# PROCESSOR.net
KiCad netlist of a schematic drawn in Altium Designer
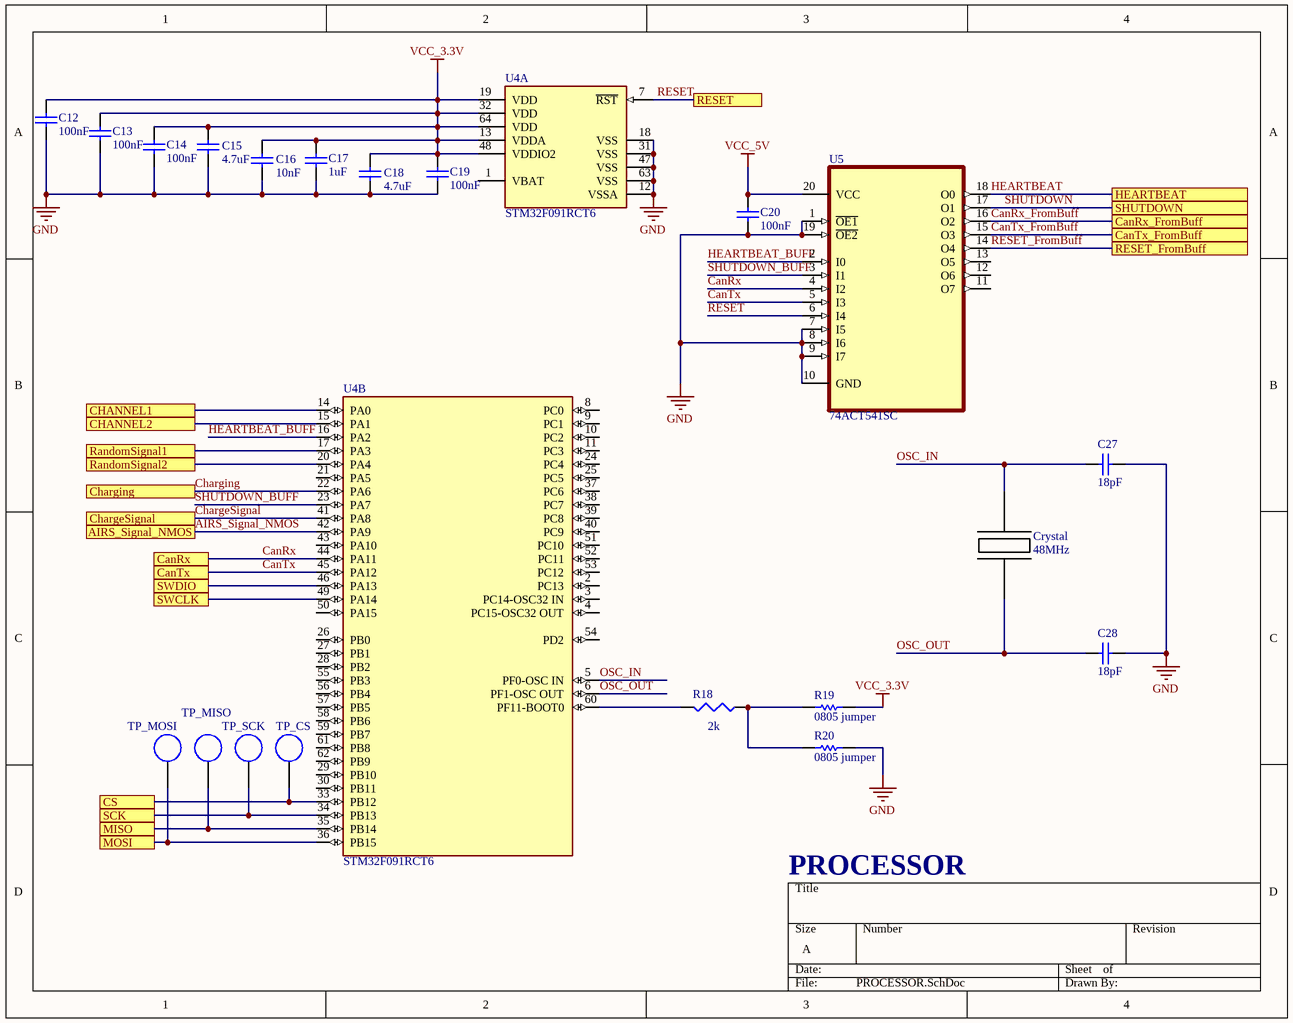
[diagram p0: PROCESSOR.SchDoc]

(export (version "E")
  (design (tool "Eeschema 10.0.6"))
  (components
    (comp (ref "C12")
      (value "100nF")
      (footprint "Cap, 5mm TH, Ceramic")
      (description "Generic Cap, 5MM TH, Ceramic")
      (fields (field (name "PUBLISHER") "T.Tallo"))
      (libsource (lib "Passives") (part "Cap, 5MM TH, Ceramic"))
    )
    (comp (ref "C13")
      (value "100nF")
      (footprint "Cap, 5mm TH, Ceramic")
      (description "Generic Cap, 5MM TH, Ceramic")
      (fields (field (name "PUBLISHER") "T.Tallo"))
      (libsource (lib "Passives") (part "Cap, 5MM TH, Ceramic"))
    )
    (comp (ref "C14")
      (value "100nF")
      (footprint "Cap, 5mm TH, Ceramic")
      (description "Generic Cap, 5MM TH, Ceramic")
      (fields (field (name "PUBLISHER") "T.Tallo"))
      (libsource (lib "Passives") (part "Cap, 5MM TH, Ceramic"))
    )
    (comp (ref "C15")
      (value "4.7uF")
      (footprint "Cap, 5mm TH, Ceramic")
      (description "Generic Cap, 5MM TH, Ceramic")
      (fields (field (name "PUBLISHER") "T.Tallo"))
      (libsource (lib "Passives") (part "Cap, 5MM TH, Ceramic"))
    )
    (comp (ref "C16")
      (value "10nF")
      (footprint "Cap, 5mm TH, Ceramic")
      (description "Generic Cap, 5MM TH, Ceramic")
      (fields (field (name "PUBLISHER") "T.Tallo"))
      (libsource (lib "Passives") (part "Cap, 5MM TH, Ceramic"))
    )
    (comp (ref "C17")
      (value "1uF")
      (footprint "Cap, 5mm TH, Ceramic")
      (description "Generic Cap, 5MM TH, Ceramic")
      (fields (field (name "PUBLISHER") "T.Tallo"))
      (libsource (lib "Passives") (part "Cap, 5MM TH, Ceramic"))
    )
    (comp (ref "C18")
      (value "4.7uF")
      (footprint "Cap, 5mm TH, Ceramic")
      (description "Generic Cap, 5MM TH, Ceramic")
      (fields (field (name "PUBLISHER") "T.Tallo"))
      (libsource (lib "Passives") (part "Cap, 5MM TH, Ceramic"))
    )
    (comp (ref "C19")
      (value "100nF")
      (footprint "Cap, 5mm TH, Ceramic")
      (description "Generic Cap, 5MM TH, Ceramic")
      (fields (field (name "PUBLISHER") "T.Tallo"))
      (libsource (lib "Passives") (part "Cap, 5MM TH, Ceramic"))
    )
    (comp (ref "C20")
      (value "100nF")
      (footprint "Cap, 5mm TH, Ceramic")
      (description "Generic Cap, 5MM TH, Ceramic")
      (fields (field (name "PUBLISHER") "T.Tallo"))
      (libsource (lib "Passives") (part "Cap, 5MM TH, Ceramic"))
    )
    (comp (ref "C27")
      (value "18pF")
      (footprint "Cap, 5mm TH, Ceramic")
      (description "Generic Cap, 5MM TH, Ceramic")
      (fields (field (name "PUBLISHER") "T.Tallo"))
      (libsource (lib "Passives") (part "Cap, 5MM TH, Ceramic"))
    )
    (comp (ref "C28")
      (value "18pF")
      (footprint "Cap, 5mm TH, Ceramic")
      (description "Generic Cap, 5MM TH, Ceramic")
      (fields (field (name "PUBLISHER") "T.Tallo"))
      (libsource (lib "Passives") (part "Cap, 5MM TH, Ceramic"))
    )
    (comp (ref "Crystal")
      (value "48MHz")
      (footprint "CrystalOscillator")
      (libsource (lib "Embedded") (part "CrystalOscillator"))
    )
    (comp (ref "R18")
      (value "2k")
      (footprint "1/4W TH Resistor")
      (description "Generic TH Resistor")
      (fields (field (name "PUBLISHER") "T.Tallo"))
      (libsource (lib "Passives") (part "Resistor, TH"))
    )
    (comp (ref "R19")
      (value "0805 jumper")
      (footprint "RESC2013X60X35LL20T20")
      (description "Chip Resistor, 0 Ohm, +/- 5%, 0.125 W, -55 to 155 degC, 0805 (2012 Metric) , RoHS, Tape and Reel")
      (fields (field (name "MANUFACTURER") "Samsung Electro-Mechanics"))
      (libsource (lib "Altium Content Vault") (part "RES-2"))
    )
    (comp (ref "R20")
      (value "0805 jumper")
      (footprint "RESC2013X60X35LL20T20")
      (description "Chip Resistor, 0 Ohm, +/- 5%, 0.125 W, -55 to 155 degC, 0805 (2012 Metric) , RoHS, Tape and Reel")
      (fields (field (name "MANUFACTURER") "Samsung Electro-Mechanics"))
      (libsource (lib "Altium Content Vault") (part "RES-2"))
    )
    (comp (ref "TP_CS")
      (value "5015")
      (footprint "5015")
      (description "SMD Test Point")
      (fields (field (name "MANUFACTURER") "Keystone Electronics") (field (name "PUBLISHER") "T.Tallo"))
      (libsource (lib "Connectors") (part "5015"))
    )
    (comp (ref "TP_MISO")
      (value "5015")
      (footprint "5015")
      (description "SMD Test Point")
      (fields (field (name "MANUFACTURER") "Keystone Electronics") (field (name "PUBLISHER") "T.Tallo"))
      (libsource (lib "Connectors") (part "5015"))
    )
    (comp (ref "TP_MOSI")
      (value "5015")
      (footprint "5015")
      (description "SMD Test Point")
      (fields (field (name "MANUFACTURER") "Keystone Electronics") (field (name "PUBLISHER") "T.Tallo"))
      (libsource (lib "Connectors") (part "5015"))
    )
    (comp (ref "TP_SCK")
      (value "5015")
      (footprint "5015")
      (description "SMD Test Point")
      (fields (field (name "MANUFACTURER") "Keystone Electronics") (field (name "PUBLISHER") "T.Tallo"))
      (libsource (lib "Connectors") (part "5015"))
    )
    (comp (ref "U4")
      (value "STM32F091RCT6")
      (footprint "FP-LQFP64-5W-MFG")
      (description "IC MCU 32BIT 256KB FLASH 64LQFP")
      (fields
        (field (name "OCTOPART") "https://octopart.com/stm32f091rct6-stmicroelectronics-51988683")
        (field (name "MANUFACTURER") "STMicroelectronics")
      )
      (libsource (lib "BMS_MasterboardUpdated") (part "CMP-12105-000069-1"))
    )
    (comp (ref "U5")
      (value "74ACT541SC")
      (footprint "SOIC127P1032X265-20N")
      (description "Buffer, Non-Inverting 1 Element 8 Bit per Element 3-State Output 20-SOIC")
      (fields (field (name "MF") "ON Semiconductor"))
      (libsource (lib "74ACT541SC") (part "74ACT541SC"))
    )
  )
  (nets
    (net (code "1") (name "/AIRS_Signal_NMOS") (class "Default")
      (node (ref "U4") (pin "42") (pinfunction "PA9_42") (pintype "bidirectional"))
    )
    (net (code "2") (name "/CHANNEL1") (class "Default")
      (node (ref "U4") (pin "14") (pinfunction "PA0_14") (pintype "bidirectional"))
    )
    (net (code "3") (name "/CHANNEL2") (class "Default")
      (node (ref "U4") (pin "15") (pinfunction "PA1_15") (pintype "bidirectional"))
    )
    (net (code "4") (name "/CS") (class "Default")
      (node (ref "TP_CS") (pin "1") (pinfunction "1_1") (pintype "passive"))
      (node (ref "U4") (pin "33") (pinfunction "PB12_33") (pintype "bidirectional"))
    )
    (net (code "5") (name "/CanRx") (class "Default")
      (node (ref "U4") (pin "44") (pinfunction "PA11_44") (pintype "bidirectional"))
      (node (ref "U5") (pin "4") (pinfunction "I2_4") (pintype "input"))
    )
    (net (code "6") (name "/CanRx_FromBuff") (class "Default")
      (node (ref "U5") (pin "16") (pinfunction "O2_16") (pintype "output"))
    )
    (net (code "7") (name "/CanTx") (class "Default")
      (node (ref "U4") (pin "45") (pinfunction "PA12_45") (pintype "bidirectional"))
      (node (ref "U5") (pin "5") (pinfunction "I3_5") (pintype "input"))
    )
    (net (code "8") (name "/CanTx_FromBuff") (class "Default")
      (node (ref "U5") (pin "15") (pinfunction "O3_15") (pintype "output"))
    )
    (net (code "9") (name "/ChargeSignal") (class "Default")
      (node (ref "U4") (pin "41") (pinfunction "PA8_41") (pintype "bidirectional"))
    )
    (net (code "10") (name "/Charging") (class "Default")
      (node (ref "U4") (pin "22") (pinfunction "PA6_22") (pintype "bidirectional"))
    )
    (net (code "11") (name "/HEARTBEAT") (class "Default")
      (node (ref "U5") (pin "18") (pinfunction "O0_18") (pintype "output"))
    )
    (net (code "12") (name "/HEARTBEAT_BUFF") (class "Default")
      (node (ref "U4") (pin "16") (pinfunction "PA2_16") (pintype "bidirectional"))
      (node (ref "U5") (pin "2") (pinfunction "I0_2") (pintype "input"))
    )
    (net (code "13") (name "/MISO") (class "Default")
      (node (ref "TP_MISO") (pin "1") (pinfunction "1_1") (pintype "passive"))
      (node (ref "U4") (pin "35") (pinfunction "PB14_35") (pintype "bidirectional"))
    )
    (net (code "14") (name "/MOSI") (class "Default")
      (node (ref "TP_MOSI") (pin "1") (pinfunction "1_1") (pintype "passive"))
      (node (ref "U4") (pin "36") (pinfunction "PB15_36") (pintype "bidirectional"))
    )
    (net (code "15") (name "/OSC_IN") (class "Default")
      (node (ref "C27") (pin "2") (pinfunction "Neg_2") (pintype "passive"))
      (node (ref "Crystal") (pin "2") (pinfunction "2_2") (pintype "passive"))
      (node (ref "U4") (pin "5") (pinfunction "PF0-OSC_IN_5") (pintype "bidirectional"))
    )
    (net (code "16") (name "/OSC_OUT") (class "Default")
      (node (ref "C28") (pin "2") (pinfunction "Neg_2") (pintype "passive"))
      (node (ref "Crystal") (pin "1") (pinfunction "1_1") (pintype "passive"))
      (node (ref "U4") (pin "6") (pinfunction "PF1-OSC_OUT_6") (pintype "bidirectional"))
    )
    (net (code "17") (name "/RESET") (class "Default")
      (node (ref "U4") (pin "7") (pinfunction "~{RST}_7") (pintype "input"))
      (node (ref "U5") (pin "6") (pinfunction "I4_6") (pintype "input"))
    )
    (net (code "18") (name "/RESET_FromBuff") (class "Default")
      (node (ref "U5") (pin "14") (pinfunction "O4_14") (pintype "output"))
    )
    (net (code "19") (name "/RandomSignal1") (class "Default")
      (node (ref "U4") (pin "17") (pinfunction "PA3_17") (pintype "bidirectional"))
    )
    (net (code "20") (name "/RandomSignal2") (class "Default")
      (node (ref "U4") (pin "20") (pinfunction "PA4_20") (pintype "bidirectional"))
    )
    (net (code "21") (name "/SCK") (class "Default")
      (node (ref "TP_SCK") (pin "1") (pinfunction "1_1") (pintype "passive"))
      (node (ref "U4") (pin "34") (pinfunction "PB13_34") (pintype "bidirectional"))
    )
    (net (code "22") (name "/SHUTDOWN") (class "Default")
      (node (ref "U5") (pin "17") (pinfunction "O1_17") (pintype "output"))
    )
    (net (code "23") (name "/SHUTDOWN_BUFF") (class "Default")
      (node (ref "U4") (pin "23") (pinfunction "PA7_23") (pintype "bidirectional"))
      (node (ref "U5") (pin "3") (pinfunction "I1_3") (pintype "input"))
    )
    (net (code "24") (name "/SWCLK") (class "Default")
      (node (ref "U4") (pin "49") (pinfunction "PA14_49") (pintype "bidirectional"))
    )
    (net (code "25") (name "/SWDIO") (class "Default")
      (node (ref "U4") (pin "46") (pinfunction "PA13_46") (pintype "bidirectional"))
    )
    (net (code "26") (name "GND") (class "Default")
      (node (ref "C12") (pin "1") (pinfunction "Pos_1") (pintype "passive"))
      (node (ref "C13") (pin "1") (pinfunction "Pos_1") (pintype "passive"))
      (node (ref "C14") (pin "1") (pinfunction "Pos_1") (pintype "passive"))
      (node (ref "C15") (pin "1") (pinfunction "Pos_1") (pintype "passive"))
      (node (ref "C16") (pin "1") (pinfunction "Pos_1") (pintype "passive"))
      (node (ref "C17") (pin "1") (pinfunction "Pos_1") (pintype "passive"))
      (node (ref "C18") (pin "1") (pinfunction "Pos_1") (pintype "passive"))
      (node (ref "C19") (pin "1") (pinfunction "Pos_1") (pintype "passive"))
      (node (ref "C20") (pin "1") (pinfunction "Pos_1") (pintype "passive"))
      (node (ref "C27") (pin "1") (pinfunction "Pos_1") (pintype "passive"))
      (node (ref "C28") (pin "1") (pinfunction "Pos_1") (pintype "passive"))
      (node (ref "R20") (pin "1") (pinfunction "1_1") (pintype "passive"))
      (node (ref "U4") (pin "12") (pinfunction "VSSA_12") (pintype "power_in"))
      (node (ref "U4") (pin "18") (pinfunction "VSS_18") (pintype "power_in"))
      (node (ref "U4") (pin "31") (pinfunction "VSS_31") (pintype "power_in"))
      (node (ref "U4") (pin "47") (pinfunction "VSS_47") (pintype "power_in"))
      (node (ref "U4") (pin "63") (pinfunction "VSS_63") (pintype "power_in"))
      (node (ref "U5") (pin "1") (pinfunction "~{OE1}_1") (pintype "input"))
      (node (ref "U5") (pin "10") (pinfunction "GND_10") (pintype "passive"))
      (node (ref "U5") (pin "19") (pinfunction "~{OE2}_19") (pintype "input"))
      (node (ref "U5") (pin "7") (pinfunction "I5_7") (pintype "input"))
      (node (ref "U5") (pin "8") (pinfunction "I6_8") (pintype "input"))
      (node (ref "U5") (pin "9") (pinfunction "I7_9") (pintype "input"))
    )
    (net (code "27") (name "Net-(R18-Pad1)") (class "Default")
      (node (ref "R18") (pin "1") (pinfunction "1_1") (pintype "passive"))
      (node (ref "R19") (pin "1") (pinfunction "1_1") (pintype "passive"))
      (node (ref "R20") (pin "2") (pinfunction "2_2") (pintype "passive"))
    )
    (net (code "28") (name "Net-(U4B-PF11-BOOT0)") (class "Default")
      (node (ref "R18") (pin "2") (pinfunction "2_2") (pintype "passive"))
      (node (ref "U4") (pin "60") (pinfunction "PF11-BOOT0_60") (pintype "bidirectional"))
    )
    (net (code "29") (name "VCC_3.3V") (class "Default")
      (node (ref "C12") (pin "2") (pinfunction "Neg_2") (pintype "passive"))
      (node (ref "C13") (pin "2") (pinfunction "Neg_2") (pintype "passive"))
      (node (ref "C14") (pin "2") (pinfunction "Neg_2") (pintype "passive"))
      (node (ref "C15") (pin "2") (pinfunction "Neg_2") (pintype "passive"))
      (node (ref "C16") (pin "2") (pinfunction "Neg_2") (pintype "passive"))
      (node (ref "C17") (pin "2") (pinfunction "Neg_2") (pintype "passive"))
      (node (ref "C18") (pin "2") (pinfunction "Neg_2") (pintype "passive"))
      (node (ref "C19") (pin "2") (pinfunction "Neg_2") (pintype "passive"))
      (node (ref "R19") (pin "2") (pinfunction "2_2") (pintype "passive"))
      (node (ref "U4") (pin "13") (pinfunction "VDDA_13") (pintype "power_in"))
      (node (ref "U4") (pin "19") (pinfunction "VDD_19") (pintype "power_in"))
      (node (ref "U4") (pin "32") (pinfunction "VDD_32") (pintype "power_in"))
      (node (ref "U4") (pin "48") (pinfunction "VDDIO2_48") (pintype "power_in"))
      (node (ref "U4") (pin "64") (pinfunction "VDD_64") (pintype "power_in"))
    )
    (net (code "30") (name "VCC_5V") (class "Default")
      (node (ref "C20") (pin "2") (pinfunction "Neg_2") (pintype "passive"))
      (node (ref "U5") (pin "20") (pinfunction "VCC_20") (pintype "power_in"))
    )
    (net (code "31") (name "unconnected-(U4A-VBAT-Pad1)") (class "Default")
      (node (ref "U4") (pin "1") (pinfunction "VBAT_1") (pintype "power_in"))
    )
    (net (code "32") (name "unconnected-(U4B-PA5-Pad21)") (class "Default")
      (node (ref "U4") (pin "21") (pinfunction "PA5_21") (pintype "bidirectional"))
    )
    (net (code "33") (name "unconnected-(U4B-PA10-Pad43)") (class "Default")
      (node (ref "U4") (pin "43") (pinfunction "PA10_43") (pintype "bidirectional"))
    )
    (net (code "34") (name "unconnected-(U4B-PA15-Pad50)") (class "Default")
      (node (ref "U4") (pin "50") (pinfunction "PA15_50") (pintype "bidirectional"))
    )
    (net (code "35") (name "unconnected-(U4B-PB0-Pad26)") (class "Default")
      (node (ref "U4") (pin "26") (pinfunction "PB0_26") (pintype "bidirectional"))
    )
    (net (code "36") (name "unconnected-(U4B-PB1-Pad27)") (class "Default")
      (node (ref "U4") (pin "27") (pinfunction "PB1_27") (pintype "bidirectional"))
    )
    (net (code "37") (name "unconnected-(U4B-PB2-Pad28)") (class "Default")
      (node (ref "U4") (pin "28") (pinfunction "PB2_28") (pintype "bidirectional"))
    )
    (net (code "38") (name "unconnected-(U4B-PB3-Pad55)") (class "Default")
      (node (ref "U4") (pin "55") (pinfunction "PB3_55") (pintype "bidirectional"))
    )
    (net (code "39") (name "unconnected-(U4B-PB4-Pad56)") (class "Default")
      (node (ref "U4") (pin "56") (pinfunction "PB4_56") (pintype "bidirectional"))
    )
    (net (code "40") (name "unconnected-(U4B-PB5-Pad57)") (class "Default")
      (node (ref "U4") (pin "57") (pinfunction "PB5_57") (pintype "bidirectional"))
    )
    (net (code "41") (name "unconnected-(U4B-PB6-Pad58)") (class "Default")
      (node (ref "U4") (pin "58") (pinfunction "PB6_58") (pintype "bidirectional"))
    )
    (net (code "42") (name "unconnected-(U4B-PB7-Pad59)") (class "Default")
      (node (ref "U4") (pin "59") (pinfunction "PB7_59") (pintype "bidirectional"))
    )
    (net (code "43") (name "unconnected-(U4B-PB8-Pad61)") (class "Default")
      (node (ref "U4") (pin "61") (pinfunction "PB8_61") (pintype "bidirectional"))
    )
    (net (code "44") (name "unconnected-(U4B-PB9-Pad62)") (class "Default")
      (node (ref "U4") (pin "62") (pinfunction "PB9_62") (pintype "bidirectional"))
    )
    (net (code "45") (name "unconnected-(U4B-PB10-Pad29)") (class "Default")
      (node (ref "U4") (pin "29") (pinfunction "PB10_29") (pintype "bidirectional"))
    )
    (net (code "46") (name "unconnected-(U4B-PB11-Pad30)") (class "Default")
      (node (ref "U4") (pin "30") (pinfunction "PB11_30") (pintype "bidirectional"))
    )
    (net (code "47") (name "unconnected-(U4B-PC0-Pad8)") (class "Default")
      (node (ref "U4") (pin "8") (pinfunction "PC0_8") (pintype "bidirectional"))
    )
    (net (code "48") (name "unconnected-(U4B-PC1-Pad9)") (class "Default")
      (node (ref "U4") (pin "9") (pinfunction "PC1_9") (pintype "bidirectional"))
    )
    (net (code "49") (name "unconnected-(U4B-PC2-Pad10)") (class "Default")
      (node (ref "U4") (pin "10") (pinfunction "PC2_10") (pintype "bidirectional"))
    )
    (net (code "50") (name "unconnected-(U4B-PC3-Pad11)") (class "Default")
      (node (ref "U4") (pin "11") (pinfunction "PC3_11") (pintype "bidirectional"))
    )
    (net (code "51") (name "unconnected-(U4B-PC4-Pad24)") (class "Default")
      (node (ref "U4") (pin "24") (pinfunction "PC4_24") (pintype "bidirectional"))
    )
    (net (code "52") (name "unconnected-(U4B-PC5-Pad25)") (class "Default")
      (node (ref "U4") (pin "25") (pinfunction "PC5_25") (pintype "bidirectional"))
    )
    (net (code "53") (name "unconnected-(U4B-PC6-Pad37)") (class "Default")
      (node (ref "U4") (pin "37") (pinfunction "PC6_37") (pintype "bidirectional"))
    )
    (net (code "54") (name "unconnected-(U4B-PC7-Pad38)") (class "Default")
      (node (ref "U4") (pin "38") (pinfunction "PC7_38") (pintype "bidirectional"))
    )
    (net (code "55") (name "unconnected-(U4B-PC8-Pad39)") (class "Default")
      (node (ref "U4") (pin "39") (pinfunction "PC8_39") (pintype "bidirectional"))
    )
    (net (code "56") (name "unconnected-(U4B-PC9-Pad40)") (class "Default")
      (node (ref "U4") (pin "40") (pinfunction "PC9_40") (pintype "bidirectional"))
    )
    (net (code "57") (name "unconnected-(U4B-PC10-Pad51)") (class "Default")
      (node (ref "U4") (pin "51") (pinfunction "PC10_51") (pintype "bidirectional"))
    )
    (net (code "58") (name "unconnected-(U4B-PC11-Pad52)") (class "Default")
      (node (ref "U4") (pin "52") (pinfunction "PC11_52") (pintype "bidirectional"))
    )
    (net (code "59") (name "unconnected-(U4B-PC12-Pad53)") (class "Default")
      (node (ref "U4") (pin "53") (pinfunction "PC12_53") (pintype "bidirectional"))
    )
    (net (code "60") (name "unconnected-(U4B-PC13-Pad2)") (class "Default")
      (node (ref "U4") (pin "2") (pinfunction "PC13_2") (pintype "bidirectional"))
    )
    (net (code "61") (name "unconnected-(U4B-PC14-OSC32_IN-Pad3)") (class "Default")
      (node (ref "U4") (pin "3") (pinfunction "PC14-OSC32_IN_3") (pintype "bidirectional"))
    )
    (net (code "62") (name "unconnected-(U4B-PC15-OSC32_OUT-Pad4)") (class "Default")
      (node (ref "U4") (pin "4") (pinfunction "PC15-OSC32_OUT_4") (pintype "bidirectional"))
    )
    (net (code "63") (name "unconnected-(U4B-PD2-Pad54)") (class "Default")
      (node (ref "U4") (pin "54") (pinfunction "PD2_54") (pintype "bidirectional"))
    )
    (net (code "64") (name "unconnected-(U5-O5-Pad13)") (class "Default")
      (node (ref "U5") (pin "13") (pinfunction "O5_13") (pintype "output"))
    )
    (net (code "65") (name "unconnected-(U5-O6-Pad12)") (class "Default")
      (node (ref "U5") (pin "12") (pinfunction "O6_12") (pintype "output"))
    )
    (net (code "66") (name "unconnected-(U5-O7-Pad11)") (class "Default")
      (node (ref "U5") (pin "11") (pinfunction "O7_11") (pintype "output"))
    )
  )
)
